# FK723MK1_ZGT6_DSUB.net
KiCad netlist of a schematic drawn in Altium Designer
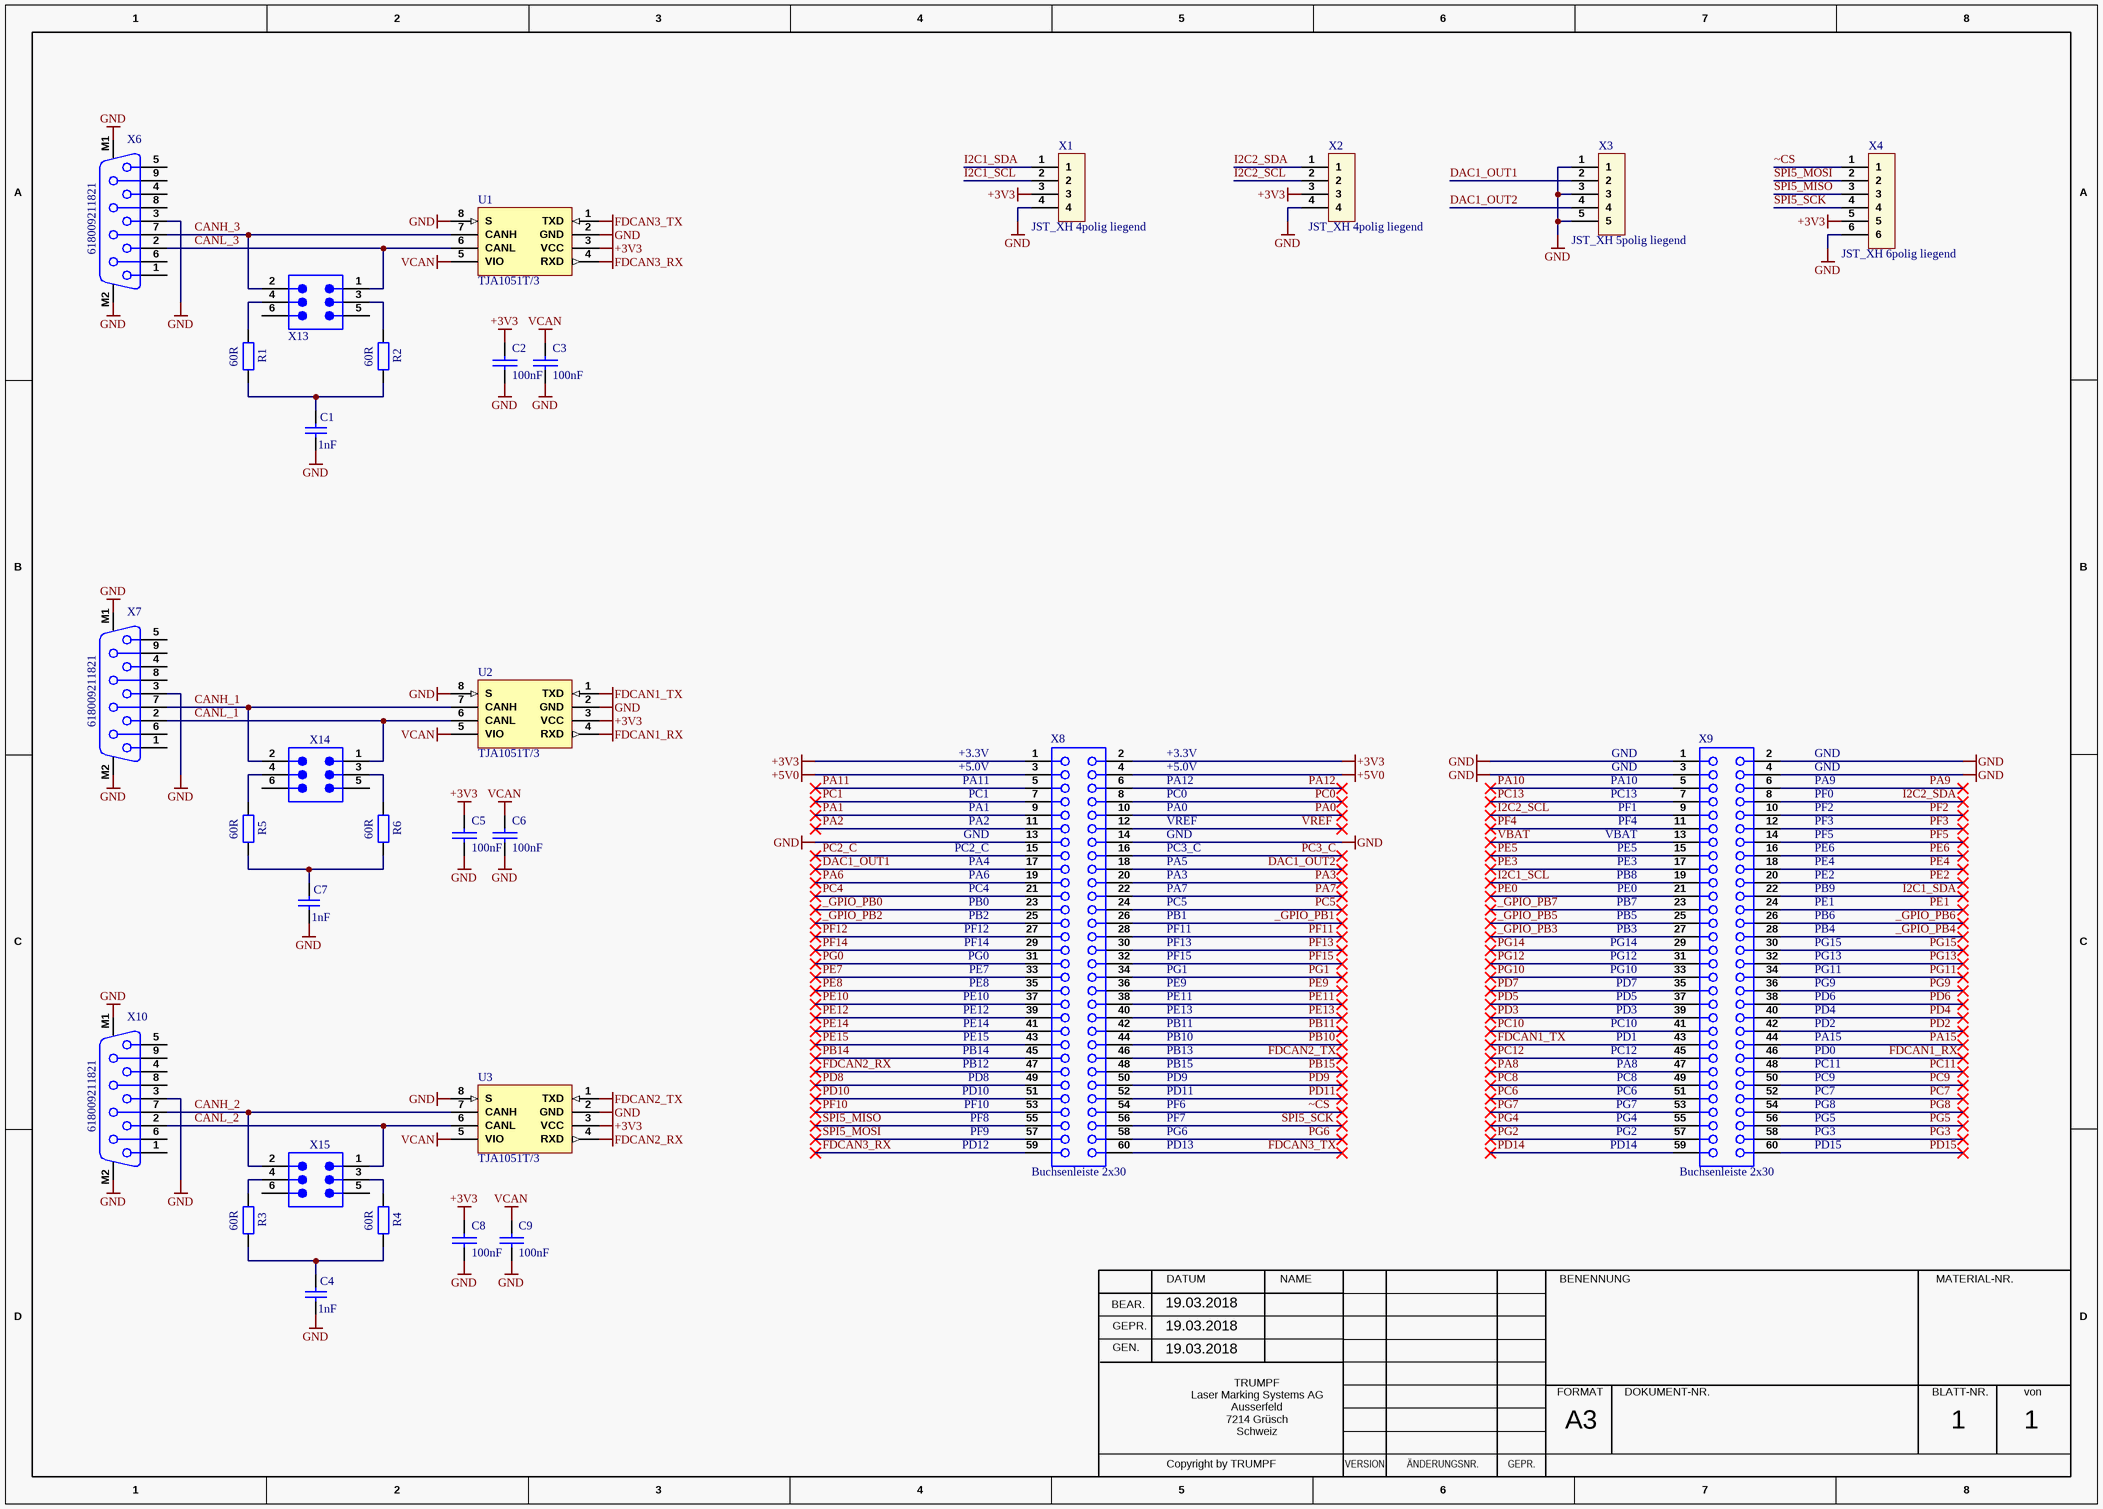
[diagram p0: FK723MK1_ZGT6_DSUB.SchDoc]

(export (version "E")
  (design (tool "Eeschema 10.0.6"))
  (components
    (comp (ref "C1")
      (value "1nF")
      (footprint "WCAP-CSGP_0603_L1.6W0.8H0.8_Reflow")
      (description "WCAP-CSGP Multilayer Ceramic Chip Capacitor, General Purpose, size 0603, 1nF, 10V")
      (fields
        (field (name "MANUFACTURER PART NUMBER") "885012006014")
        (field (name "MANUFACTURER") "Wurth Elektronik")
      )
      (libsource (lib "Altium_WCAP-CSGP (rev25c)") (part "885012006014"))
    )
    (comp (ref "C2")
      (value "100nF")
      (footprint "0402")
      (description "100nF 16V 10% 0402")
      (libsource (lib "ChipCapacitors") (part "100nF"))
    )
    (comp (ref "C3")
      (value "100nF")
      (footprint "0402")
      (description "100nF 16V 10% 0402")
      (libsource (lib "ChipCapacitors") (part "100nF"))
    )
    (comp (ref "C4")
      (value "1nF")
      (footprint "WCAP-CSGP_0603_L1.6W0.8H0.8_Reflow")
      (description "WCAP-CSGP Multilayer Ceramic Chip Capacitor, General Purpose, size 0603, 1nF, 10V")
      (fields
        (field (name "MANUFACTURER PART NUMBER") "885012006014")
        (field (name "MANUFACTURER") "Wurth Elektronik")
      )
      (libsource (lib "Altium_WCAP-CSGP (rev25c)") (part "885012006014"))
    )
    (comp (ref "C5")
      (value "100nF")
      (footprint "0402")
      (description "100nF 16V 10% 0402")
      (libsource (lib "ChipCapacitors") (part "100nF"))
    )
    (comp (ref "C6")
      (value "100nF")
      (footprint "0402")
      (description "100nF 16V 10% 0402")
      (libsource (lib "ChipCapacitors") (part "100nF"))
    )
    (comp (ref "C7")
      (value "1nF")
      (footprint "WCAP-CSGP_0603_L1.6W0.8H0.8_Reflow")
      (description "WCAP-CSGP Multilayer Ceramic Chip Capacitor, General Purpose, size 0603, 1nF, 10V")
      (fields
        (field (name "MANUFACTURER PART NUMBER") "885012006014")
        (field (name "MANUFACTURER") "Wurth Elektronik")
      )
      (libsource (lib "Altium_WCAP-CSGP (rev25c)") (part "885012006014"))
    )
    (comp (ref "C8")
      (value "100nF")
      (footprint "0402")
      (description "100nF 16V 10% 0402")
      (libsource (lib "ChipCapacitors") (part "100nF"))
    )
    (comp (ref "C9")
      (value "100nF")
      (footprint "0402")
      (description "100nF 16V 10% 0402")
      (libsource (lib "ChipCapacitors") (part "100nF"))
    )
    (comp (ref "R1")
      (value "60R")
      (footprint "WRIS-KSKE_0805")
      (description "WRIS-KSKE Thick Film Resistor, SMT, size 0805, 0.1Ω, 0.33W, +/-1%")
      (fields
        (field (name "MANUFACTURER PART NUMBER") "560050320001")
        (field (name "MANUFACTURER") "Wurth Elektronik")
      )
      (libsource (lib "Altium_WRIS-KSKE (rev25b)") (part "560050320001"))
    )
    (comp (ref "R2")
      (value "60R")
      (footprint "WRIS-KSKE_0805")
      (description "WRIS-KSKE Thick Film Resistor, SMT, size 0805, 0.1Ω, 0.33W, +/-1%")
      (fields
        (field (name "MANUFACTURER PART NUMBER") "560050320001")
        (field (name "MANUFACTURER") "Wurth Elektronik")
      )
      (libsource (lib "Altium_WRIS-KSKE (rev25b)") (part "560050320001"))
    )
    (comp (ref "R3")
      (value "60R")
      (footprint "WRIS-KSKE_0805")
      (description "WRIS-KSKE Thick Film Resistor, SMT, size 0805, 0.1Ω, 0.33W, +/-1%")
      (fields
        (field (name "MANUFACTURER PART NUMBER") "560050320001")
        (field (name "MANUFACTURER") "Wurth Elektronik")
      )
      (libsource (lib "Altium_WRIS-KSKE (rev25b)") (part "560050320001"))
    )
    (comp (ref "R4")
      (value "60R")
      (footprint "WRIS-KSKE_0805")
      (description "WRIS-KSKE Thick Film Resistor, SMT, size 0805, 0.1Ω, 0.33W, +/-1%")
      (fields
        (field (name "MANUFACTURER PART NUMBER") "560050320001")
        (field (name "MANUFACTURER") "Wurth Elektronik")
      )
      (libsource (lib "Altium_WRIS-KSKE (rev25b)") (part "560050320001"))
    )
    (comp (ref "R5")
      (value "60R")
      (footprint "WRIS-KSKE_0805")
      (description "WRIS-KSKE Thick Film Resistor, SMT, size 0805, 0.1Ω, 0.33W, +/-1%")
      (fields
        (field (name "MANUFACTURER PART NUMBER") "560050320001")
        (field (name "MANUFACTURER") "Wurth Elektronik")
      )
      (libsource (lib "Altium_WRIS-KSKE (rev25b)") (part "560050320001"))
    )
    (comp (ref "R6")
      (value "60R")
      (footprint "WRIS-KSKE_0805")
      (description "WRIS-KSKE Thick Film Resistor, SMT, size 0805, 0.1Ω, 0.33W, +/-1%")
      (fields
        (field (name "MANUFACTURER PART NUMBER") "560050320001")
        (field (name "MANUFACTURER") "Wurth Elektronik")
      )
      (libsource (lib "Altium_WRIS-KSKE (rev25b)") (part "560050320001"))
    )
    (comp (ref "U1") (value "TJA1051T/3") (footprint "SO-8") (libsource (lib "TJA1051") (part "TJA1051T/3")))
    (comp (ref "U2") (value "TJA1051T/3") (footprint "SO-8") (libsource (lib "TJA1051") (part "TJA1051T/3")))
    (comp (ref "U3") (value "TJA1051T/3") (footprint "SO-8") (libsource (lib "TJA1051") (part "TJA1051T/3")))
    (comp (ref "X1")
      (value "JST_XH 4polig liegend")
      (footprint "JST_XH 4polig, liegend")
      (libsource (lib "JST_XH") (part "JST_XH 4polig"))
    )
    (comp (ref "X2")
      (value "JST_XH 4polig liegend")
      (footprint "JST_XH 4polig, liegend")
      (libsource (lib "JST_XH") (part "JST_XH 4polig"))
    )
    (comp (ref "X3")
      (value "JST_XH 5polig liegend")
      (footprint "JST_XH 5polig, liegend")
      (libsource (lib "JST_XH") (part "JST_XH 5polig"))
    )
    (comp (ref "X4")
      (value "JST_XH 6polig liegend")
      (footprint "JST_XH 6polig, liegend")
      (libsource (lib "JST_XH") (part "JST_XH 6polig"))
    )
    (comp (ref "X6")
      (value "618009211821")
      (footprint "618009211821")
      (description "WR-DSUB 8.08mm Female PCB Connector without Hex Screw, THT, Angled, 9p")
      (fields (field (name "MANUFACTURER") "Wurth Elektronik"))
      (libsource (lib "Altium_WR-DSUB (rev25b)") (part "618009211821"))
    )
    (comp (ref "X7")
      (value "618009211821")
      (footprint "618009211821")
      (description "WR-DSUB 8.08mm Female PCB Connector without Hex Screw, THT, Angled, 9p")
      (fields (field (name "MANUFACTURER") "Wurth Elektronik"))
      (libsource (lib "Altium_WR-DSUB (rev25b)") (part "618009211821"))
    )
    (comp (ref "X8")
      (value "Buchsenleiste 2x30")
      (footprint "Buchsenleiste 2x30polig")
      (libsource (lib "Buchsenleiste60polig") (part "Buchsenleiste 2x30"))
    )
    (comp (ref "X9")
      (value "Buchsenleiste 2x30")
      (footprint "Buchsenleiste 2x30polig")
      (libsource (lib "Buchsenleiste60polig") (part "Buchsenleiste 2x30"))
    )
    (comp (ref "X10")
      (value "618009211821")
      (footprint "618009211821")
      (description "WR-DSUB 8.08mm Female PCB Connector without Hex Screw, THT, Angled, 9p")
      (fields (field (name "MANUFACTURER") "Wurth Elektronik"))
      (libsource (lib "Altium_WR-DSUB (rev25b)") (part "618009211821"))
    )
    (comp (ref "X13")
      (value "61300621121")
      (footprint "61300621121")
      (description "WR-PHD Pin Header, THT, Vertical, pitch 2.54mm, 2 Row, 6P")
      (fields (field (name "MANUFACTURER") "Wurth Elektronik"))
      (libsource (lib "Altium_WR-PHD (rev24a)") (part "61300621121"))
    )
    (comp (ref "X14")
      (value "61300621121")
      (footprint "61300621121")
      (description "WR-PHD Pin Header, THT, Vertical, pitch 2.54mm, 2 Row, 6P")
      (fields (field (name "MANUFACTURER") "Wurth Elektronik"))
      (libsource (lib "Altium_WR-PHD (rev24a)") (part "61300621121"))
    )
    (comp (ref "X15")
      (value "61300621121")
      (footprint "61300621121")
      (description "WR-PHD Pin Header, THT, Vertical, pitch 2.54mm, 2 Row, 6P")
      (fields (field (name "MANUFACTURER") "Wurth Elektronik"))
      (libsource (lib "Altium_WR-PHD (rev24a)") (part "61300621121"))
    )
  )
  (nets
    (net (code "1") (name "+3V3") (class "Default")
      (node (ref "C2") (pin "1") (pinfunction "1_1") (pintype "passive"))
      (node (ref "C5") (pin "1") (pinfunction "1_1") (pintype "passive"))
      (node (ref "C8") (pin "1") (pinfunction "1_1") (pintype "passive"))
      (node (ref "U1") (pin "3") (pinfunction "VCC_3") (pintype "power_in"))
      (node (ref "U2") (pin "3") (pinfunction "VCC_3") (pintype "power_in"))
      (node (ref "U3") (pin "3") (pinfunction "VCC_3") (pintype "power_in"))
      (node (ref "X1") (pin "3") (pinfunction "3_3") (pintype "passive"))
      (node (ref "X2") (pin "3") (pinfunction "3_3") (pintype "passive"))
      (node (ref "X4") (pin "5") (pinfunction "5_5") (pintype "passive"))
      (node (ref "X8") (pin "1") (pinfunction "1_1") (pintype "passive"))
      (node (ref "X8") (pin "2") (pinfunction "2_2") (pintype "passive"))
    )
    (net (code "2") (name "+5V0") (class "Default")
      (node (ref "X8") (pin "3") (pinfunction "3_3") (pintype "passive"))
      (node (ref "X8") (pin "4") (pinfunction "4_4") (pintype "passive"))
    )
    (net (code "3") (name "/CANH_1") (class "Default")
      (node (ref "U2") (pin "7") (pinfunction "CANH_7") (pintype "passive"))
      (node (ref "X14") (pin "2") (pinfunction "2_2") (pintype "passive"))
      (node (ref "X7") (pin "7") (pinfunction "7_7") (pintype "passive"))
    )
    (net (code "4") (name "/CANH_2") (class "Default")
      (node (ref "U3") (pin "7") (pinfunction "CANH_7") (pintype "passive"))
      (node (ref "X10") (pin "7") (pinfunction "7_7") (pintype "passive"))
      (node (ref "X15") (pin "2") (pinfunction "2_2") (pintype "passive"))
    )
    (net (code "5") (name "/CANH_3") (class "Default")
      (node (ref "U1") (pin "7") (pinfunction "CANH_7") (pintype "passive"))
      (node (ref "X13") (pin "2") (pinfunction "2_2") (pintype "passive"))
      (node (ref "X6") (pin "7") (pinfunction "7_7") (pintype "passive"))
    )
    (net (code "6") (name "/CANL_1") (class "Default")
      (node (ref "U2") (pin "6") (pinfunction "CANL_6") (pintype "passive"))
      (node (ref "X14") (pin "1") (pinfunction "1_1") (pintype "passive"))
      (node (ref "X7") (pin "2") (pinfunction "2_2") (pintype "passive"))
    )
    (net (code "7") (name "/CANL_2") (class "Default")
      (node (ref "U3") (pin "6") (pinfunction "CANL_6") (pintype "passive"))
      (node (ref "X10") (pin "2") (pinfunction "2_2") (pintype "passive"))
      (node (ref "X15") (pin "1") (pinfunction "1_1") (pintype "passive"))
    )
    (net (code "8") (name "/CANL_3") (class "Default")
      (node (ref "U1") (pin "6") (pinfunction "CANL_6") (pintype "passive"))
      (node (ref "X13") (pin "1") (pinfunction "1_1") (pintype "passive"))
      (node (ref "X6") (pin "2") (pinfunction "2_2") (pintype "passive"))
    )
    (net (code "9") (name "/DAC1_OUT1") (class "Default")
      (node (ref "X3") (pin "2") (pinfunction "2_2") (pintype "passive"))
      (node (ref "X8") (pin "17") (pinfunction "17_17") (pintype "passive"))
    )
    (net (code "10") (name "/DAC1_OUT2") (class "Default")
      (node (ref "X3") (pin "4") (pinfunction "4_4") (pintype "passive"))
      (node (ref "X8") (pin "18") (pinfunction "18_18") (pintype "passive"))
    )
    (net (code "11") (name "/I2C1_SCL") (class "Default")
      (node (ref "X1") (pin "2") (pinfunction "2_2") (pintype "passive"))
      (node (ref "X9") (pin "19") (pinfunction "19_19") (pintype "passive"))
    )
    (net (code "12") (name "/I2C1_SDA") (class "Default")
      (node (ref "X1") (pin "1") (pinfunction "1_1") (pintype "passive"))
      (node (ref "X9") (pin "22") (pinfunction "22_22") (pintype "passive"))
    )
    (net (code "13") (name "/I2C2_SCL") (class "Default")
      (node (ref "X2") (pin "2") (pinfunction "2_2") (pintype "passive"))
      (node (ref "X9") (pin "9") (pinfunction "9_9") (pintype "passive"))
    )
    (net (code "14") (name "/I2C2_SDA") (class "Default")
      (node (ref "X2") (pin "1") (pinfunction "1_1") (pintype "passive"))
      (node (ref "X9") (pin "8") (pinfunction "8_8") (pintype "passive"))
    )
    (net (code "15") (name "/PA0") (class "Default")
      (node (ref "X8") (pin "10") (pinfunction "10_10") (pintype "passive+no_connect"))
    )
    (net (code "16") (name "/PA1") (class "Default")
      (node (ref "X8") (pin "9") (pinfunction "9_9") (pintype "passive+no_connect"))
    )
    (net (code "17") (name "/PA2") (class "Default")
      (node (ref "X8") (pin "11") (pinfunction "11_11") (pintype "passive+no_connect"))
    )
    (net (code "18") (name "/PA3") (class "Default")
      (node (ref "X8") (pin "20") (pinfunction "20_20") (pintype "passive+no_connect"))
    )
    (net (code "19") (name "/PA6") (class "Default")
      (node (ref "X8") (pin "19") (pinfunction "19_19") (pintype "passive+no_connect"))
    )
    (net (code "20") (name "/PA7") (class "Default")
      (node (ref "X8") (pin "22") (pinfunction "22_22") (pintype "passive+no_connect"))
    )
    (net (code "21") (name "/PA8") (class "Default")
      (node (ref "X9") (pin "47") (pinfunction "47_47") (pintype "passive+no_connect"))
    )
    (net (code "22") (name "/PA9") (class "Default")
      (node (ref "X9") (pin "6") (pinfunction "6_6") (pintype "passive+no_connect"))
    )
    (net (code "23") (name "/PA10") (class "Default")
      (node (ref "X9") (pin "5") (pinfunction "5_5") (pintype "passive+no_connect"))
    )
    (net (code "24") (name "/PA11") (class "Default")
      (node (ref "X8") (pin "5") (pinfunction "5_5") (pintype "passive+no_connect"))
    )
    (net (code "25") (name "/PA12") (class "Default")
      (node (ref "X8") (pin "6") (pinfunction "6_6") (pintype "passive+no_connect"))
    )
    (net (code "26") (name "/PA15") (class "Default")
      (node (ref "X9") (pin "44") (pinfunction "44_44") (pintype "passive+no_connect"))
    )
    (net (code "27") (name "/PB10") (class "Default")
      (node (ref "X8") (pin "44") (pinfunction "44_44") (pintype "passive+no_connect"))
    )
    (net (code "28") (name "/PB11") (class "Default")
      (node (ref "X8") (pin "42") (pinfunction "42_42") (pintype "passive+no_connect"))
    )
    (net (code "29") (name "/PB14") (class "Default")
      (node (ref "X8") (pin "45") (pinfunction "45_45") (pintype "passive+no_connect"))
    )
    (net (code "30") (name "/PB15") (class "Default")
      (node (ref "X8") (pin "48") (pinfunction "48_48") (pintype "passive+no_connect"))
    )
    (net (code "31") (name "/PC0") (class "Default")
      (node (ref "X8") (pin "8") (pinfunction "8_8") (pintype "passive+no_connect"))
    )
    (net (code "32") (name "/PC1") (class "Default")
      (node (ref "X8") (pin "7") (pinfunction "7_7") (pintype "passive+no_connect"))
    )
    (net (code "33") (name "/PC2_C") (class "Default")
      (node (ref "X8") (pin "15") (pinfunction "15_15") (pintype "passive+no_connect"))
    )
    (net (code "34") (name "/PC3_C") (class "Default")
      (node (ref "X8") (pin "16") (pinfunction "16_16") (pintype "passive+no_connect"))
    )
    (net (code "35") (name "/PC4") (class "Default")
      (node (ref "X8") (pin "21") (pinfunction "21_21") (pintype "passive+no_connect"))
    )
    (net (code "36") (name "/PC5") (class "Default")
      (node (ref "X8") (pin "24") (pinfunction "24_24") (pintype "passive+no_connect"))
    )
    (net (code "37") (name "/PC6") (class "Default")
      (node (ref "X9") (pin "51") (pinfunction "51_51") (pintype "passive+no_connect"))
    )
    (net (code "38") (name "/PC7") (class "Default")
      (node (ref "X9") (pin "52") (pinfunction "52_52") (pintype "passive+no_connect"))
    )
    (net (code "39") (name "/PC8") (class "Default")
      (node (ref "X9") (pin "49") (pinfunction "49_49") (pintype "passive+no_connect"))
    )
    (net (code "40") (name "/PC9") (class "Default")
      (node (ref "X9") (pin "50") (pinfunction "50_50") (pintype "passive+no_connect"))
    )
    (net (code "41") (name "/PC10") (class "Default")
      (node (ref "X9") (pin "41") (pinfunction "41_41") (pintype "passive+no_connect"))
    )
    (net (code "42") (name "/PC11") (class "Default")
      (node (ref "X9") (pin "48") (pinfunction "48_48") (pintype "passive+no_connect"))
    )
    (net (code "43") (name "/PC12") (class "Default")
      (node (ref "X9") (pin "45") (pinfunction "45_45") (pintype "passive+no_connect"))
    )
    (net (code "44") (name "/PC13") (class "Default")
      (node (ref "X9") (pin "7") (pinfunction "7_7") (pintype "passive+no_connect"))
    )
    (net (code "45") (name "/PD2") (class "Default")
      (node (ref "X9") (pin "42") (pinfunction "42_42") (pintype "passive+no_connect"))
    )
    (net (code "46") (name "/PD3") (class "Default")
      (node (ref "X9") (pin "39") (pinfunction "39_39") (pintype "passive+no_connect"))
    )
    (net (code "47") (name "/PD4") (class "Default")
      (node (ref "X9") (pin "40") (pinfunction "40_40") (pintype "passive+no_connect"))
    )
    (net (code "48") (name "/PD5") (class "Default")
      (node (ref "X9") (pin "37") (pinfunction "37_37") (pintype "passive+no_connect"))
    )
    (net (code "49") (name "/PD6") (class "Default")
      (node (ref "X9") (pin "38") (pinfunction "38_38") (pintype "passive+no_connect"))
    )
    (net (code "50") (name "/PD7") (class "Default")
      (node (ref "X9") (pin "35") (pinfunction "35_35") (pintype "passive+no_connect"))
    )
    (net (code "51") (name "/PD8") (class "Default")
      (node (ref "X8") (pin "49") (pinfunction "49_49") (pintype "passive+no_connect"))
    )
    (net (code "52") (name "/PD9") (class "Default")
      (node (ref "X8") (pin "50") (pinfunction "50_50") (pintype "passive+no_connect"))
    )
    (net (code "53") (name "/PD10") (class "Default")
      (node (ref "X8") (pin "51") (pinfunction "51_51") (pintype "passive+no_connect"))
    )
    (net (code "54") (name "/PD11") (class "Default")
      (node (ref "X8") (pin "52") (pinfunction "52_52") (pintype "passive+no_connect"))
    )
    (net (code "55") (name "/PD14") (class "Default")
      (node (ref "X9") (pin "59") (pinfunction "59_59") (pintype "passive+no_connect"))
    )
    (net (code "56") (name "/PD15") (class "Default")
      (node (ref "X9") (pin "60") (pinfunction "60_60") (pintype "passive+no_connect"))
    )
    (net (code "57") (name "/PE0") (class "Default")
      (node (ref "X9") (pin "21") (pinfunction "21_21") (pintype "passive+no_connect"))
    )
    (net (code "58") (name "/PE1") (class "Default")
      (node (ref "X9") (pin "24") (pinfunction "24_24") (pintype "passive+no_connect"))
    )
    (net (code "59") (name "/PE2") (class "Default")
      (node (ref "X9") (pin "20") (pinfunction "20_20") (pintype "passive+no_connect"))
    )
    (net (code "60") (name "/PE3") (class "Default")
      (node (ref "X9") (pin "17") (pinfunction "17_17") (pintype "passive+no_connect"))
    )
    (net (code "61") (name "/PE4") (class "Default")
      (node (ref "X9") (pin "18") (pinfunction "18_18") (pintype "passive+no_connect"))
    )
    (net (code "62") (name "/PE5") (class "Default")
      (node (ref "X9") (pin "15") (pinfunction "15_15") (pintype "passive+no_connect"))
    )
    (net (code "63") (name "/PE6") (class "Default")
      (node (ref "X9") (pin "16") (pinfunction "16_16") (pintype "passive+no_connect"))
    )
    (net (code "64") (name "/PE7") (class "Default")
      (node (ref "X8") (pin "33") (pinfunction "33_33") (pintype "passive+no_connect"))
    )
    (net (code "65") (name "/PE8") (class "Default")
      (node (ref "X8") (pin "35") (pinfunction "35_35") (pintype "passive+no_connect"))
    )
    (net (code "66") (name "/PE9") (class "Default")
      (node (ref "X8") (pin "36") (pinfunction "36_36") (pintype "passive+no_connect"))
    )
    (net (code "67") (name "/PE10") (class "Default")
      (node (ref "X8") (pin "37") (pinfunction "37_37") (pintype "passive+no_connect"))
    )
    (net (code "68") (name "/PE11") (class "Default")
      (node (ref "X8") (pin "38") (pinfunction "38_38") (pintype "passive+no_connect"))
    )
    (net (code "69") (name "/PE12") (class "Default")
      (node (ref "X8") (pin "39") (pinfunction "39_39") (pintype "passive+no_connect"))
    )
    (net (code "70") (name "/PE13") (class "Default")
      (node (ref "X8") (pin "40") (pinfunction "40_40") (pintype "passive+no_connect"))
    )
    (net (code "71") (name "/PE14") (class "Default")
      (node (ref "X8") (pin "41") (pinfunction "41_41") (pintype "passive+no_connect"))
    )
    (net (code "72") (name "/PE15") (class "Default")
      (node (ref "X8") (pin "43") (pinfunction "43_43") (pintype "passive+no_connect"))
    )
    (net (code "73") (name "/PF2") (class "Default")
      (node (ref "X9") (pin "10") (pinfunction "10_10") (pintype "passive+no_connect"))
    )
    (net (code "74") (name "/PF3") (class "Default")
      (node (ref "X9") (pin "12") (pinfunction "12_12") (pintype "passive+no_connect"))
    )
    (net (code "75") (name "/PF4") (class "Default")
      (node (ref "X9") (pin "11") (pinfunction "11_11") (pintype "passive+no_connect"))
    )
    (net (code "76") (name "/PF5") (class "Default")
      (node (ref "X9") (pin "14") (pinfunction "14_14") (pintype "passive+no_connect"))
    )
    (net (code "77") (name "/PF10") (class "Default")
      (node (ref "X8") (pin "53") (pinfunction "53_53") (pintype "passive+no_connect"))
    )
    (net (code "78") (name "/PF11") (class "Default")
      (node (ref "X8") (pin "28") (pinfunction "28_28") (pintype "passive+no_connect"))
    )
    (net (code "79") (name "/PF12") (class "Default")
      (node (ref "X8") (pin "27") (pinfunction "27_27") (pintype "passive+no_connect"))
    )
    (net (code "80") (name "/PF13") (class "Default")
      (node (ref "X8") (pin "30") (pinfunction "30_30") (pintype "passive+no_connect"))
    )
    (net (code "81") (name "/PF14") (class "Default")
      (node (ref "X8") (pin "29") (pinfunction "29_29") (pintype "passive+no_connect"))
    )
    (net (code "82") (name "/PF15") (class "Default")
      (node (ref "X8") (pin "32") (pinfunction "32_32") (pintype "passive+no_connect"))
    )
    (net (code "83") (name "/PG0") (class "Default")
      (node (ref "X8") (pin "31") (pinfunction "31_31") (pintype "passive+no_connect"))
    )
    (net (code "84") (name "/PG1") (class "Default")
      (node (ref "X8") (pin "34") (pinfunction "34_34") (pintype "passive+no_connect"))
    )
    (net (code "85") (name "/PG2") (class "Default")
      (node (ref "X9") (pin "57") (pinfunction "57_57") (pintype "passive+no_connect"))
    )
    (net (code "86") (name "/PG3") (class "Default")
      (node (ref "X9") (pin "58") (pinfunction "58_58") (pintype "passive+no_connect"))
    )
    (net (code "87") (name "/PG4") (class "Default")
      (node (ref "X9") (pin "55") (pinfunction "55_55") (pintype "passive+no_connect"))
    )
    (net (code "88") (name "/PG5") (class "Default")
      (node (ref "X9") (pin "56") (pinfunction "56_56") (pintype "passive+no_connect"))
    )
    (net (code "89") (name "/PG6") (class "Default")
      (node (ref "X8") (pin "58") (pinfunction "58_58") (pintype "passive+no_connect"))
    )
    (net (code "90") (name "/PG7") (class "Default")
      (node (ref "X9") (pin "53") (pinfunction "53_53") (pintype "passive+no_connect"))
    )
    (net (code "91") (name "/PG8") (class "Default")
      (node (ref "X9") (pin "54") (pinfunction "54_54") (pintype "passive+no_connect"))
    )
    (net (code "92") (name "/PG9") (class "Default")
      (node (ref "X9") (pin "36") (pinfunction "36_36") (pintype "passive+no_connect"))
    )
    (net (code "93") (name "/PG10") (class "Default")
      (node (ref "X9") (pin "33") (pinfunction "33_33") (pintype "passive+no_connect"))
    )
    (net (code "94") (name "/PG11") (class "Default")
      (node (ref "X9") (pin "34") (pinfunction "34_34") (pintype "passive+no_connect"))
    )
    (net (code "95") (name "/PG12") (class "Default")
      (node (ref "X9") (pin "31") (pinfunction "31_31") (pintype "passive+no_connect"))
    )
    (net (code "96") (name "/PG13") (class "Default")
      (node (ref "X9") (pin "32") (pinfunction "32_32") (pintype "passive+no_connect"))
    )
    (net (code "97") (name "/PG14") (class "Default")
      (node (ref "X9") (pin "29") (pinfunction "29_29") (pintype "passive+no_connect"))
    )
    (net (code "98") (name "/PG15") (class "Default")
      (node (ref "X9") (pin "30") (pinfunction "30_30") (pintype "passive+no_connect"))
    )
    (net (code "99") (name "/SPI5_MISO") (class "Default")
      (node (ref "X4") (pin "3") (pinfunction "3_3") (pintype "passive"))
      (node (ref "X8") (pin "55") (pinfunction "55_55") (pintype "passive"))
    )
    (net (code "100") (name "/SPI5_MOSI") (class "Default")
      (node (ref "X4") (pin "2") (pinfunction "2_2") (pintype "passive"))
      (node (ref "X8") (pin "57") (pinfunction "57_57") (pintype "passive"))
    )
    (net (code "101") (name "/SPI5_SCK") (class "Default")
      (node (ref "X4") (pin "4") (pinfunction "4_4") (pintype "passive"))
      (node (ref "X8") (pin "56") (pinfunction "56_56") (pintype "passive"))
    )
    (net (code "102") (name "/VBAT") (class "Default")
      (node (ref "X9") (pin "13") (pinfunction "13_13") (pintype "passive+no_connect"))
    )
    (net (code "103") (name "/VREF") (class "Default")
      (node (ref "X8") (pin "12") (pinfunction "12_12") (pintype "passive+no_connect"))
    )
    (net (code "104") (name "/_GPIO_PB0") (class "Default")
      (node (ref "X8") (pin "23") (pinfunction "23_23") (pintype "passive+no_connect"))
    )
    (net (code "105") (name "/_GPIO_PB1") (class "Default")
      (node (ref "X8") (pin "26") (pinfunction "26_26") (pintype "passive+no_connect"))
    )
    (net (code "106") (name "/_GPIO_PB2") (class "Default")
      (node (ref "X8") (pin "25") (pinfunction "25_25") (pintype "passive+no_connect"))
    )
    (net (code "107") (name "/_GPIO_PB3") (class "Default")
      (node (ref "X9") (pin "27") (pinfunction "27_27") (pintype "passive+no_connect"))
    )
    (net (code "108") (name "/_GPIO_PB4") (class "Default")
      (node (ref "X9") (pin "28") (pinfunction "28_28") (pintype "passive+no_connect"))
    )
    (net (code "109") (name "/_GPIO_PB5") (class "Default")
      (node (ref "X9") (pin "25") (pinfunction "25_25") (pintype "passive+no_connect"))
    )
    (net (code "110") (name "/_GPIO_PB6") (class "Default")
      (node (ref "X9") (pin "26") (pinfunction "26_26") (pintype "passive+no_connect"))
    )
    (net (code "111") (name "/_GPIO_PB7") (class "Default")
      (node (ref "X9") (pin "23") (pinfunction "23_23") (pintype "passive+no_connect"))
    )
    (net (code "112") (name "/~CS") (class "Default")
      (node (ref "X4") (pin "1") (pinfunction "1_1") (pintype "passive"))
      (node (ref "X8") (pin "54") (pinfunction "54_54") (pintype "passive"))
    )
    (net (code "113") (name "FDCAN1_RX") (class "Default")
      (node (ref "U2") (pin "4") (pinfunction "RXD_4") (pintype "output"))
      (node (ref "X9") (pin "46") (pinfunction "46_46") (pintype "passive"))
    )
    (net (code "114") (name "FDCAN1_TX") (class "Default")
      (node (ref "U2") (pin "1") (pinfunction "TXD_1") (pintype "input"))
      (node (ref "X9") (pin "43") (pinfunction "43_43") (pintype "passive"))
    )
    (net (code "115") (name "FDCAN2_RX") (class "Default")
      (node (ref "U3") (pin "4") (pinfunction "RXD_4") (pintype "output"))
      (node (ref "X8") (pin "47") (pinfunction "47_47") (pintype "passive"))
    )
    (net (code "116") (name "FDCAN2_TX") (class "Default")
      (node (ref "U3") (pin "1") (pinfunction "TXD_1") (pintype "input"))
      (node (ref "X8") (pin "46") (pinfunction "46_46") (pintype "passive"))
    )
    (net (code "117") (name "FDCAN3_RX") (class "Default")
      (node (ref "U1") (pin "4") (pinfunction "RXD_4") (pintype "output"))
      (node (ref "X8") (pin "59") (pinfunction "59_59") (pintype "passive"))
    )
    (net (code "118") (name "FDCAN3_TX") (class "Default")
      (node (ref "U1") (pin "1") (pinfunction "TXD_1") (pintype "input"))
      (node (ref "X8") (pin "60") (pinfunction "60_60") (pintype "passive"))
    )
    (net (code "119") (name "GND") (class "Default")
      (node (ref "C1") (pin "1") (pinfunction "1_1") (pintype "passive"))
      (node (ref "C2") (pin "2") (pinfunction "2_2") (pintype "passive"))
      (node (ref "C3") (pin "2") (pinfunction "2_2") (pintype "passive"))
      (node (ref "C4") (pin "1") (pinfunction "1_1") (pintype "passive"))
      (node (ref "C5") (pin "2") (pinfunction "2_2") (pintype "passive"))
      (node (ref "C6") (pin "2") (pinfunction "2_2") (pintype "passive"))
      (node (ref "C7") (pin "1") (pinfunction "1_1") (pintype "passive"))
      (node (ref "C8") (pin "2") (pinfunction "2_2") (pintype "passive"))
      (node (ref "C9") (pin "2") (pinfunction "2_2") (pintype "passive"))
      (node (ref "U1") (pin "2") (pinfunction "GND_2") (pintype "power_in"))
      (node (ref "U1") (pin "8") (pinfunction "S_8") (pintype "input"))
      (node (ref "U2") (pin "2") (pinfunction "GND_2") (pintype "power_in"))
      (node (ref "U2") (pin "8") (pinfunction "S_8") (pintype "input"))
      (node (ref "U3") (pin "2") (pinfunction "GND_2") (pintype "power_in"))
      (node (ref "U3") (pin "8") (pinfunction "S_8") (pintype "input"))
      (node (ref "X1") (pin "4") (pinfunction "4_4") (pintype "passive"))
      (node (ref "X10") (pin "3") (pinfunction "3_3") (pintype "passive"))
      (node (ref "X10") (pin "M1") (pinfunction "M1_M1") (pintype "passive"))
      (node (ref "X10") (pin "M2") (pinfunction "M2_M2") (pintype "passive"))
      (node (ref "X2") (pin "4") (pinfunction "4_4") (pintype "passive"))
      (node (ref "X3") (pin "1") (pinfunction "1_1") (pintype "passive"))
      (node (ref "X3") (pin "3") (pinfunction "3_3") (pintype "passive"))
      (node (ref "X3") (pin "5") (pinfunction "5_5") (pintype "passive"))
      (node (ref "X4") (pin "6") (pinfunction "6_6") (pintype "passive"))
      (node (ref "X6") (pin "3") (pinfunction "3_3") (pintype "passive"))
      (node (ref "X6") (pin "M1") (pinfunction "M1_M1") (pintype "passive"))
      (node (ref "X6") (pin "M2") (pinfunction "M2_M2") (pintype "passive"))
      (node (ref "X7") (pin "3") (pinfunction "3_3") (pintype "passive"))
      (node (ref "X7") (pin "M1") (pinfunction "M1_M1") (pintype "passive"))
      (node (ref "X7") (pin "M2") (pinfunction "M2_M2") (pintype "passive"))
      (node (ref "X8") (pin "13") (pinfunction "13_13") (pintype "passive"))
      (node (ref "X8") (pin "14") (pinfunction "14_14") (pintype "passive"))
      (node (ref "X9") (pin "1") (pinfunction "1_1") (pintype "passive"))
      (node (ref "X9") (pin "2") (pinfunction "2_2") (pintype "passive"))
      (node (ref "X9") (pin "3") (pinfunction "3_3") (pintype "passive"))
      (node (ref "X9") (pin "4") (pinfunction "4_4") (pintype "passive"))
    )
    (net (code "120") (name "Net-(C1-Pad2)") (class "Default")
      (node (ref "C1") (pin "2") (pinfunction "2_2") (pintype "passive"))
      (node (ref "R1") (pin "1") (pinfunction "1_1") (pintype "passive"))
      (node (ref "R2") (pin "1") (pinfunction "1_1") (pintype "passive"))
    )
    (net (code "121") (name "Net-(C4-Pad2)") (class "Default")
      (node (ref "C4") (pin "2") (pinfunction "2_2") (pintype "passive"))
      (node (ref "R3") (pin "1") (pinfunction "1_1") (pintype "passive"))
      (node (ref "R4") (pin "1") (pinfunction "1_1") (pintype "passive"))
    )
    (net (code "122") (name "Net-(C7-Pad2)") (class "Default")
      (node (ref "C7") (pin "2") (pinfunction "2_2") (pintype "passive"))
      (node (ref "R5") (pin "1") (pinfunction "1_1") (pintype "passive"))
      (node (ref "R6") (pin "1") (pinfunction "1_1") (pintype "passive"))
    )
    (net (code "123") (name "Net-(R1-Pad2)") (class "Default")
      (node (ref "R1") (pin "2") (pinfunction "2_2") (pintype "passive"))
      (node (ref "X13") (pin "4") (pinfunction "4_4") (pintype "passive"))
    )
    (net (code "124") (name "Net-(R2-Pad2)") (class "Default")
      (node (ref "R2") (pin "2") (pinfunction "2_2") (pintype "passive"))
      (node (ref "X13") (pin "3") (pinfunction "3_3") (pintype "passive"))
    )
    (net (code "125") (name "Net-(R3-Pad2)") (class "Default")
      (node (ref "R3") (pin "2") (pinfunction "2_2") (pintype "passive"))
      (node (ref "X15") (pin "4") (pinfunction "4_4") (pintype "passive"))
    )
    (net (code "126") (name "Net-(R4-Pad2)") (class "Default")
      (node (ref "R4") (pin "2") (pinfunction "2_2") (pintype "passive"))
      (node (ref "X15") (pin "3") (pinfunction "3_3") (pintype "passive"))
    )
    (net (code "127") (name "Net-(R5-Pad2)") (class "Default")
      (node (ref "R5") (pin "2") (pinfunction "2_2") (pintype "passive"))
      (node (ref "X14") (pin "4") (pinfunction "4_4") (pintype "passive"))
    )
    (net (code "128") (name "Net-(R6-Pad2)") (class "Default")
      (node (ref "R6") (pin "2") (pinfunction "2_2") (pintype "passive"))
      (node (ref "X14") (pin "3") (pinfunction "3_3") (pintype "passive"))
    )
    (net (code "129") (name "VCAN") (class "Default")
      (node (ref "C3") (pin "1") (pinfunction "1_1") (pintype "passive"))
      (node (ref "C6") (pin "1") (pinfunction "1_1") (pintype "passive"))
      (node (ref "C9") (pin "1") (pinfunction "1_1") (pintype "passive"))
      (node (ref "U1") (pin "5") (pinfunction "VIO_5") (pintype "power_in"))
      (node (ref "U2") (pin "5") (pinfunction "VIO_5") (pintype "power_in"))
      (node (ref "U3") (pin "5") (pinfunction "VIO_5") (pintype "power_in"))
    )
    (net (code "130") (name "unconnected-(X6-Pad1)") (class "Default")
      (node (ref "X6") (pin "1") (pinfunction "1_1") (pintype "passive"))
    )
    (net (code "131") (name "unconnected-(X6-Pad4)") (class "Default")
      (node (ref "X6") (pin "4") (pinfunction "4_4") (pintype "passive"))
    )
    (net (code "132") (name "unconnected-(X6-Pad5)") (class "Default")
      (node (ref "X6") (pin "5") (pinfunction "5_5") (pintype "passive"))
    )
    (net (code "133") (name "unconnected-(X6-Pad6)") (class "Default")
      (node (ref "X6") (pin "6") (pinfunction "6_6") (pintype "passive"))
    )
    (net (code "134") (name "unconnected-(X6-Pad8)") (class "Default")
      (node (ref "X6") (pin "8") (pinfunction "8_8") (pintype "passive"))
    )
    (net (code "135") (name "unconnected-(X6-Pad9)") (class "Default")
      (node (ref "X6") (pin "9") (pinfunction "9_9") (pintype "passive"))
    )
    (net (code "136") (name "unconnected-(X7-Pad1)") (class "Default")
      (node (ref "X7") (pin "1") (pinfunction "1_1") (pintype "passive"))
    )
    (net (code "137") (name "unconnected-(X7-Pad4)") (class "Default")
      (node (ref "X7") (pin "4") (pinfunction "4_4") (pintype "passive"))
    )
    (net (code "138") (name "unconnected-(X7-Pad5)") (class "Default")
      (node (ref "X7") (pin "5") (pinfunction "5_5") (pintype "passive"))
    )
    (net (code "139") (name "unconnected-(X7-Pad6)") (class "Default")
      (node (ref "X7") (pin "6") (pinfunction "6_6") (pintype "passive"))
    )
    (net (code "140") (name "unconnected-(X7-Pad8)") (class "Default")
      (node (ref "X7") (pin "8") (pinfunction "8_8") (pintype "passive"))
    )
    (net (code "141") (name "unconnected-(X7-Pad9)") (class "Default")
      (node (ref "X7") (pin "9") (pinfunction "9_9") (pintype "passive"))
    )
    (net (code "142") (name "unconnected-(X10-Pad1)") (class "Default")
      (node (ref "X10") (pin "1") (pinfunction "1_1") (pintype "passive"))
    )
    (net (code "143") (name "unconnected-(X10-Pad4)") (class "Default")
      (node (ref "X10") (pin "4") (pinfunction "4_4") (pintype "passive"))
    )
    (net (code "144") (name "unconnected-(X10-Pad5)") (class "Default")
      (node (ref "X10") (pin "5") (pinfunction "5_5") (pintype "passive"))
    )
    (net (code "145") (name "unconnected-(X10-Pad6)") (class "Default")
      (node (ref "X10") (pin "6") (pinfunction "6_6") (pintype "passive"))
    )
    (net (code "146") (name "unconnected-(X10-Pad8)") (class "Default")
      (node (ref "X10") (pin "8") (pinfunction "8_8") (pintype "passive"))
    )
    (net (code "147") (name "unconnected-(X10-Pad9)") (class "Default")
      (node (ref "X10") (pin "9") (pinfunction "9_9") (pintype "passive"))
    )
    (net (code "148") (name "unconnected-(X13-Pad5)") (class "Default")
      (node (ref "X13") (pin "5") (pinfunction "5_5") (pintype "passive"))
    )
    (net (code "149") (name "unconnected-(X13-Pad6)") (class "Default")
      (node (ref "X13") (pin "6") (pinfunction "6_6") (pintype "passive"))
    )
    (net (code "150") (name "unconnected-(X14-Pad5)") (class "Default")
      (node (ref "X14") (pin "5") (pinfunction "5_5") (pintype "passive"))
    )
    (net (code "151") (name "unconnected-(X14-Pad6)") (class "Default")
      (node (ref "X14") (pin "6") (pinfunction "6_6") (pintype "passive"))
    )
    (net (code "152") (name "unconnected-(X15-Pad5)") (class "Default")
      (node (ref "X15") (pin "5") (pinfunction "5_5") (pintype "passive"))
    )
    (net (code "153") (name "unconnected-(X15-Pad6)") (class "Default")
      (node (ref "X15") (pin "6") (pinfunction "6_6") (pintype "passive"))
    )
  )
)
